# usb-hub-1b.net
KiCad netlist of a schematic drawn in EAGLE
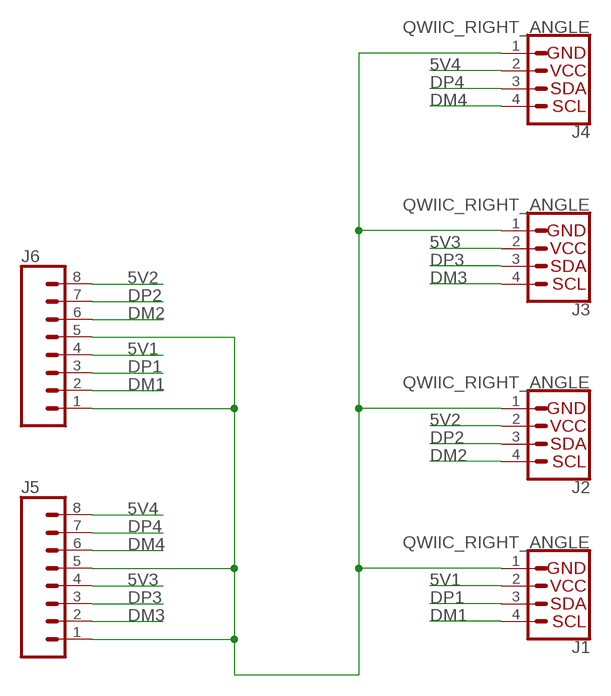
[diagram p0: schematic, sheet 1]

(export (version "E")
  (design (tool "Eeschema 10.0.6"))
  (components
    (comp (ref "J1")
      (value "QWIIC_RIGHT_ANGLE")
      (footprint "eagle-import:JST04_1MM_RA")
      (libsource (lib "eagle-import") (part "QWIIC_CONNECTORJS-1MM"))
    )
    (comp (ref "J2")
      (value "QWIIC_RIGHT_ANGLE")
      (footprint "eagle-import:JST04_1MM_RA")
      (libsource (lib "eagle-import") (part "QWIIC_CONNECTORJS-1MM"))
    )
    (comp (ref "J3")
      (value "QWIIC_RIGHT_ANGLE")
      (footprint "eagle-import:JST04_1MM_RA")
      (libsource (lib "eagle-import") (part "QWIIC_CONNECTORJS-1MM"))
    )
    (comp (ref "J4")
      (value "QWIIC_RIGHT_ANGLE")
      (footprint "eagle-import:JST04_1MM_RA")
      (libsource (lib "eagle-import") (part "QWIIC_CONNECTORJS-1MM"))
    )
    (comp (ref "J5")
      (value "CONN_08LOCK")
      (footprint "eagle-import:1X08_LOCK")
      (libsource (lib "eagle-import") (part "CONN_08LOCK"))
    )
    (comp (ref "J6")
      (value "CONN_08LOCK")
      (footprint "eagle-import:1X08_LOCK")
      (libsource (lib "eagle-import") (part "CONN_08LOCK"))
    )
  )
  (nets
    (net (code "1") (name "/5V1") (class "Default")
      (node (ref "J1") (pin "2") (pinfunction "2_2") (pintype "power_in"))
      (node (ref "J6") (pin "4") (pinfunction "4_4") (pintype "passive"))
    )
    (net (code "2") (name "/5V2") (class "Default")
      (node (ref "J2") (pin "2") (pinfunction "2_2") (pintype "power_in"))
      (node (ref "J6") (pin "8") (pinfunction "8_8") (pintype "passive"))
    )
    (net (code "3") (name "/5V3") (class "Default")
      (node (ref "J3") (pin "2") (pinfunction "2_2") (pintype "power_in"))
      (node (ref "J5") (pin "4") (pinfunction "4_4") (pintype "passive"))
    )
    (net (code "4") (name "/5V4") (class "Default")
      (node (ref "J4") (pin "2") (pinfunction "2_2") (pintype "power_in"))
      (node (ref "J5") (pin "8") (pinfunction "8_8") (pintype "passive"))
    )
    (net (code "5") (name "/DM1") (class "Default")
      (node (ref "J1") (pin "4") (pinfunction "4_4") (pintype "passive"))
      (node (ref "J6") (pin "2") (pinfunction "2_2") (pintype "passive"))
    )
    (net (code "6") (name "/DM2") (class "Default")
      (node (ref "J2") (pin "4") (pinfunction "4_4") (pintype "passive"))
      (node (ref "J6") (pin "6") (pinfunction "6_6") (pintype "passive"))
    )
    (net (code "7") (name "/DM3") (class "Default")
      (node (ref "J3") (pin "4") (pinfunction "4_4") (pintype "passive"))
      (node (ref "J5") (pin "2") (pinfunction "2_2") (pintype "passive"))
    )
    (net (code "8") (name "/DM4") (class "Default")
      (node (ref "J4") (pin "4") (pinfunction "4_4") (pintype "passive"))
      (node (ref "J5") (pin "6") (pinfunction "6_6") (pintype "passive"))
    )
    (net (code "9") (name "/DP1") (class "Default")
      (node (ref "J1") (pin "3") (pinfunction "3_3") (pintype "passive"))
      (node (ref "J6") (pin "3") (pinfunction "3_3") (pintype "passive"))
    )
    (net (code "10") (name "/DP2") (class "Default")
      (node (ref "J2") (pin "3") (pinfunction "3_3") (pintype "passive"))
      (node (ref "J6") (pin "7") (pinfunction "7_7") (pintype "passive"))
    )
    (net (code "11") (name "/DP3") (class "Default")
      (node (ref "J3") (pin "3") (pinfunction "3_3") (pintype "passive"))
      (node (ref "J5") (pin "3") (pinfunction "3_3") (pintype "passive"))
    )
    (net (code "12") (name "/DP4") (class "Default")
      (node (ref "J4") (pin "3") (pinfunction "3_3") (pintype "passive"))
      (node (ref "J5") (pin "7") (pinfunction "7_7") (pintype "passive"))
    )
    (net (code "13") (name "Net-(J1-Pad1)") (class "Default")
      (node (ref "J1") (pin "1") (pinfunction "1_1") (pintype "power_in"))
      (node (ref "J2") (pin "1") (pinfunction "1_1") (pintype "power_in"))
      (node (ref "J3") (pin "1") (pinfunction "1_1") (pintype "power_in"))
      (node (ref "J4") (pin "1") (pinfunction "1_1") (pintype "power_in"))
      (node (ref "J5") (pin "1") (pinfunction "1_1") (pintype "passive"))
      (node (ref "J5") (pin "5") (pinfunction "5_5") (pintype "passive"))
      (node (ref "J6") (pin "1") (pinfunction "1_1") (pintype "passive"))
      (node (ref "J6") (pin "5") (pinfunction "5_5") (pintype "passive"))
    )
  )
)
